# SparkFun_LilyPad_Buzzer.net
KiCad netlist of a schematic drawn in EAGLE
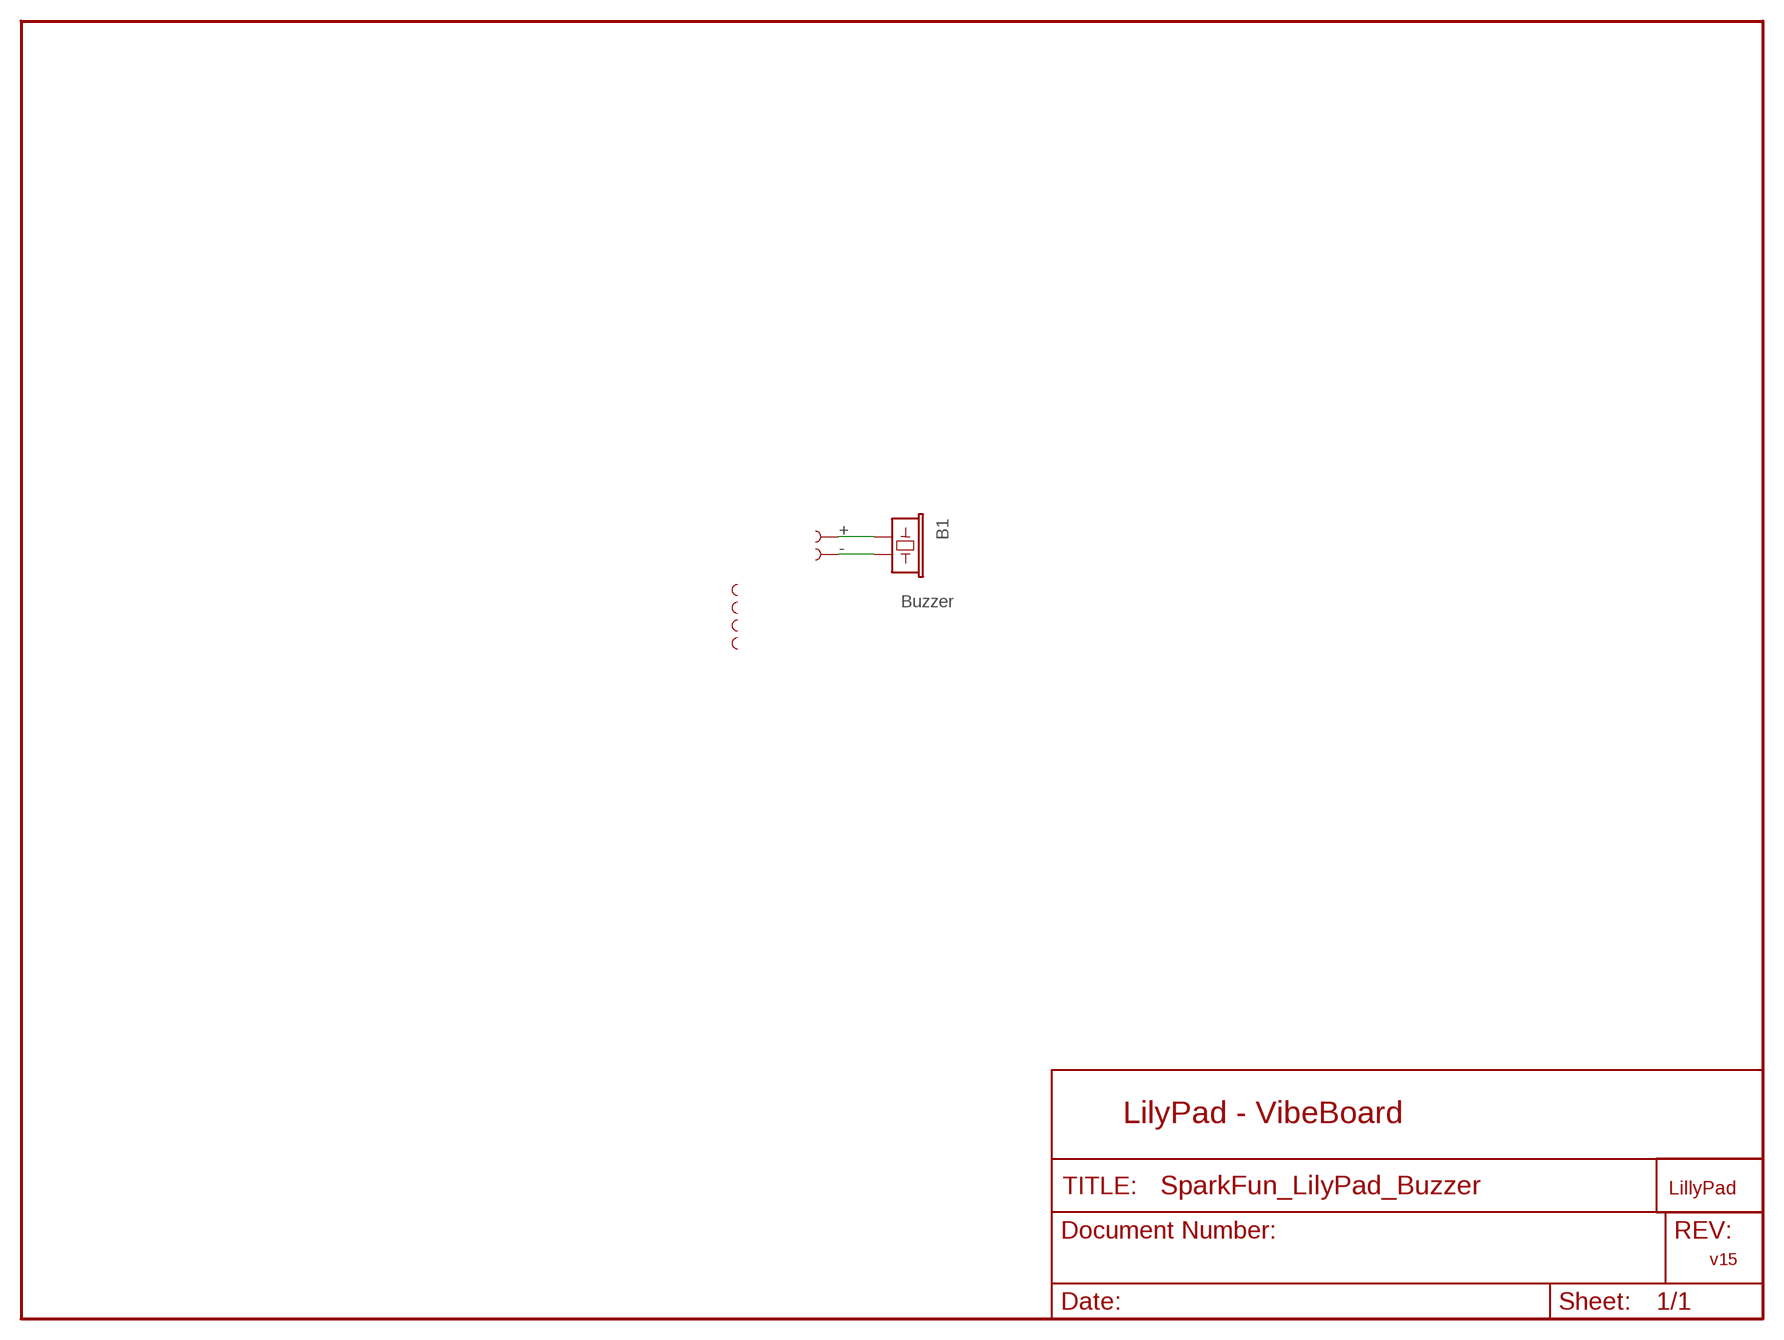
[diagram p0: schematic, sheet 1]

(export (version "E")
  (design (tool "Eeschema 10.0.6"))
  (components
    (comp (ref "B1")
      (value "Buzzer")
      (footprint "eagle-import:BUZZER-CCV")
      (libsource (lib "eagle-import") (part "BUZZERSMD2"))
    )
    (comp (ref "U$1")
      (value "SEWTAP-NOHOLE2")
      (footprint "eagle-import:PETAL-NOHOLE-2SIDE")
      (libsource (lib "eagle-import") (part "SEWTAP-NOHOLE2"))
    )
    (comp (ref "U$2")
      (value "LOGO-LPLP")
      (footprint "eagle-import:LOGO-LILYPAD")
      (libsource (lib "eagle-import") (part "LOGO-LPLP"))
    )
    (comp (ref "U$4")
      (value "SEWTAP-NOHOLE2")
      (footprint "eagle-import:PETAL-NOHOLE-2SIDE")
      (libsource (lib "eagle-import") (part "SEWTAP-NOHOLE2"))
    )
    (comp (ref "U$6")
      (value "SEWTAP-NOHOLE2")
      (footprint "eagle-import:PETAL-NOHOLE-2SIDE")
      (libsource (lib "eagle-import") (part "SEWTAP-NOHOLE2"))
    )
    (comp (ref "U$7")
      (value "SEWTAP-NOHOLE2")
      (footprint "eagle-import:PETAL-NOHOLE-2SIDE")
      (libsource (lib "eagle-import") (part "SEWTAP-NOHOLE2"))
    )
    (comp (ref "U$8")
      (value "SEWTAP6")
      (footprint "eagle-import:PETAL-SMALL-2SIDE")
      (libsource (lib "eagle-import") (part "SEWTAP6"))
    )
    (comp (ref "U$9")
      (value "SEWTAP6")
      (footprint "eagle-import:PETAL-SMALL-2SIDE")
      (libsource (lib "eagle-import") (part "SEWTAP6"))
    )
  )
  (nets
    (net (code "1") (name "/+") (class "Default")
      (node (ref "B1") (pin "+") (pinfunction "1_+") (pintype "passive"))
      (node (ref "U$9") (pin "1") (pinfunction "1_1") (pintype "bidirectional"))
    )
    (net (code "2") (name "/-") (class "Default")
      (node (ref "B1") (pin "-") (pinfunction "2_-") (pintype "passive"))
      (node (ref "U$8") (pin "1") (pinfunction "1_1") (pintype "bidirectional"))
    )
  )
)
